# 26PinSuperseal.net
KiCad netlist of a schematic drawn in Altium Designer
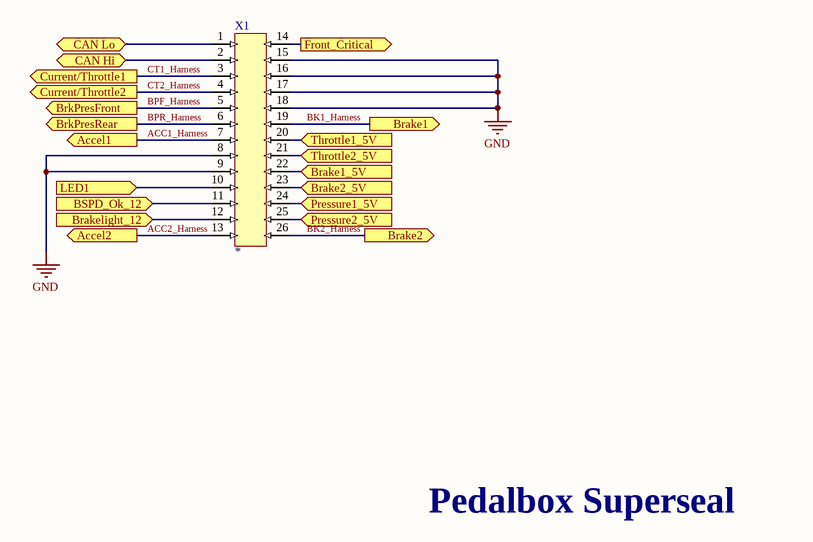
[diagram p0: 26PinSuperseal.SchDoc]

(export (version "E")
  (design (tool "Eeschema 10.0.6"))
  (components
    (comp (ref "X1")
      (value "*")
      (footprint "SUPERSEAL 26POS 90Deg")
      (description "AMP Superseal 90Deg")
      (libsource (lib "altlib") (part "CONN 26POS"))
    )
  )
  (nets
    (net (code "1") (name "/ACC1_Harness") (class "Default") (node (ref "X1") (pin "7") (pintype "input")))
    (net (code "2") (name "/ACC2_Harness") (class "Default") (node (ref "X1") (pin "13") (pintype "input")))
    (net (code "3") (name "/BK1_Harness") (class "Default") (node (ref "X1") (pin "19") (pintype "input")))
    (net (code "4") (name "/BK2_Harness") (class "Default") (node (ref "X1") (pin "26") (pintype "input")))
    (net (code "5") (name "/BPF_Harness") (class "Default") (node (ref "X1") (pin "5") (pintype "input")))
    (net (code "6") (name "/BPR_Harness") (class "Default") (node (ref "X1") (pin "6") (pintype "input")))
    (net (code "7") (name "/BSPD_Ok_12") (class "Default") (node (ref "X1") (pin "11") (pintype "input")))
    (net (code "8") (name "/Brake1_5V") (class "Default") (node (ref "X1") (pin "22") (pintype "input")))
    (net (code "9") (name "/Brake2_5V") (class "Default") (node (ref "X1") (pin "23") (pintype "input")))
    (net (code "10") (name "/Brakelight_12") (class "Default") (node (ref "X1") (pin "12") (pintype "input")))
    (net (code "11") (name "/CAN Hi") (class "Default") (node (ref "X1") (pin "2") (pintype "input")))
    (net (code "12") (name "/CAN Lo") (class "Default") (node (ref "X1") (pin "1") (pintype "input")))
    (net (code "13") (name "/CT1_Harness") (class "Default") (node (ref "X1") (pin "3") (pintype "input")))
    (net (code "14") (name "/CT2_Harness") (class "Default") (node (ref "X1") (pin "4") (pintype "input")))
    (net (code "15") (name "/Front_Critical") (class "Default")
      (node (ref "X1") (pin "14") (pintype "input"))
    )
    (net (code "16") (name "/LED1") (class "Default") (node (ref "X1") (pin "10") (pintype "input")))
    (net (code "17") (name "/Pressure1_5V") (class "Default") (node (ref "X1") (pin "24") (pintype "input")))
    (net (code "18") (name "/Pressure2_5V") (class "Default") (node (ref "X1") (pin "25") (pintype "input")))
    (net (code "19") (name "/Throttle1_5V") (class "Default") (node (ref "X1") (pin "20") (pintype "input")))
    (net (code "20") (name "/Throttle2_5V") (class "Default") (node (ref "X1") (pin "21") (pintype "input")))
    (net (code "21") (name "GND") (class "Default")
      (node (ref "X1") (pin "15") (pintype "input"))
      (node (ref "X1") (pin "16") (pintype "input"))
      (node (ref "X1") (pin "17") (pintype "input"))
      (node (ref "X1") (pin "18") (pintype "input"))
      (node (ref "X1") (pin "8") (pintype "input"))
      (node (ref "X1") (pin "9") (pintype "input"))
    )
  )
)
